# Schematic_KeyScreen.net
KiCad netlist of a schematic drawn in Altium Designer
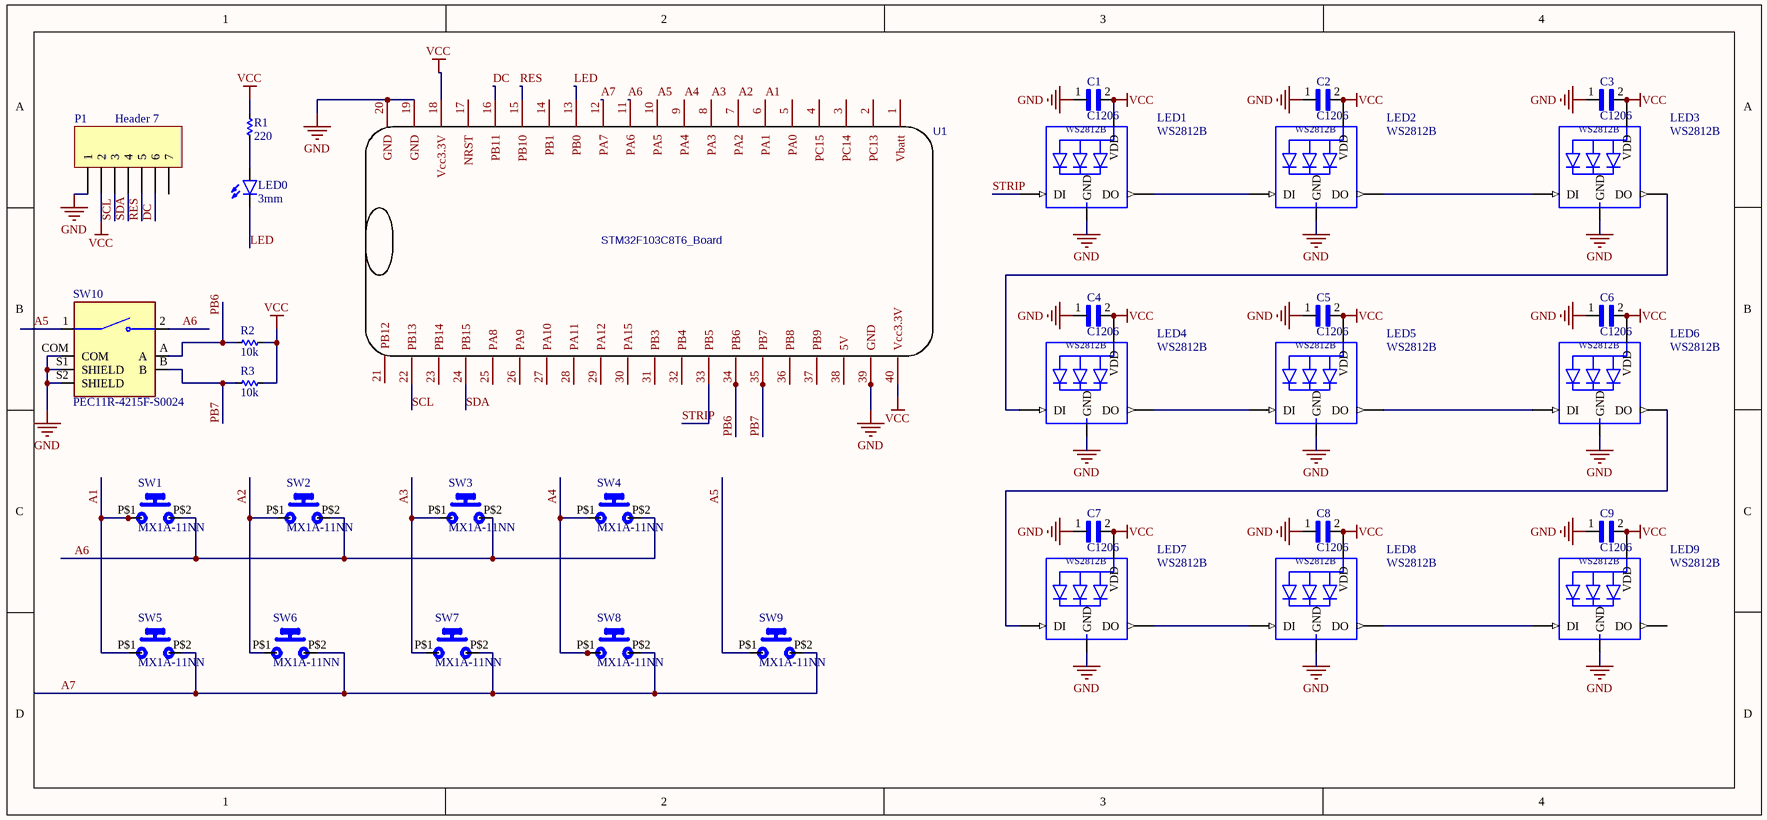
[diagram p0: Schematic_KeyScreen.SchDoc]

(export (version "E")
  (design (tool "Eeschema 10.0.6"))
  (components
    (comp (ref "C1")
      (value "C1206")
      (footprint "SnapEDApcb:CAPC3216X110N")
      (description "1ÂµF Â±10% 50V Ceramic Capacitor X7R 1206 _3216 Metric_")
      (fields (field (name "MP") "C1206C105K5RACTU") (field (name "MF") "KEMET"))
      (libsource (lib "SnapEDAsch") (part "C1206C105K5RACTU"))
    )
    (comp (ref "C2")
      (value "C1206")
      (footprint "SnapEDApcb:CAPC3216X110N")
      (description "1ÂµF Â±10% 50V Ceramic Capacitor X7R 1206 _3216 Metric_")
      (fields (field (name "MP") "C1206C105K5RACTU") (field (name "MF") "KEMET"))
      (libsource (lib "SnapEDAsch") (part "C1206C105K5RACTU"))
    )
    (comp (ref "C3")
      (value "C1206")
      (footprint "SnapEDApcb:CAPC3216X110N")
      (description "1ÂµF Â±10% 50V Ceramic Capacitor X7R 1206 _3216 Metric_")
      (fields (field (name "MP") "C1206C105K5RACTU") (field (name "MF") "KEMET"))
      (libsource (lib "SnapEDAsch") (part "C1206C105K5RACTU"))
    )
    (comp (ref "C4")
      (value "C1206")
      (footprint "SnapEDApcb:CAPC3216X110N")
      (description "1ÂµF Â±10% 50V Ceramic Capacitor X7R 1206 _3216 Metric_")
      (fields (field (name "MP") "C1206C105K5RACTU") (field (name "MF") "KEMET"))
      (libsource (lib "SnapEDAsch") (part "C1206C105K5RACTU"))
    )
    (comp (ref "C5")
      (value "C1206")
      (footprint "SnapEDApcb:CAPC3216X110N")
      (description "1ÂµF Â±10% 50V Ceramic Capacitor X7R 1206 _3216 Metric_")
      (fields (field (name "MP") "C1206C105K5RACTU") (field (name "MF") "KEMET"))
      (libsource (lib "SnapEDAsch") (part "C1206C105K5RACTU"))
    )
    (comp (ref "C6")
      (value "C1206")
      (footprint "SnapEDApcb:CAPC3216X110N")
      (description "1ÂµF Â±10% 50V Ceramic Capacitor X7R 1206 _3216 Metric_")
      (fields (field (name "MP") "C1206C105K5RACTU") (field (name "MF") "KEMET"))
      (libsource (lib "SnapEDAsch") (part "C1206C105K5RACTU"))
    )
    (comp (ref "C7")
      (value "C1206")
      (footprint "Miscellaneous Devices:3.2X1.6X1.1")
      (description "1ÂµF Â±10% 50V Ceramic Capacitor X7R 1206 _3216 Metric_")
      (fields (field (name "MP") "C1206C105K5RACTU") (field (name "MF") "KEMET"))
      (libsource (lib "SnapEDAsch") (part "C1206C105K5RACTU"))
    )
    (comp (ref "C8")
      (value "C1206")
      (footprint "Miscellaneous Devices:3.2X1.6X1.1")
      (description "1ÂµF Â±10% 50V Ceramic Capacitor X7R 1206 _3216 Metric_")
      (fields (field (name "MP") "C1206C105K5RACTU") (field (name "MF") "KEMET"))
      (libsource (lib "SnapEDAsch") (part "C1206C105K5RACTU"))
    )
    (comp (ref "C9")
      (value "C1206")
      (footprint "SnapEDApcb:CAPC3216X110N")
      (description "1ÂµF Â±10% 50V Ceramic Capacitor X7R 1206 _3216 Metric_")
      (fields (field (name "MP") "C1206C105K5RACTU") (field (name "MF") "KEMET"))
      (libsource (lib "SnapEDAsch") (part "C1206C105K5RACTU"))
    )
    (comp (ref "LED0")
      (value "3mm")
      (footprint "LED3MM")
      (description "Green 569nm LED Indication - Discrete 1.9V Radial")
      (fields (field (name "MP") "TLLG4400") (field (name "MF") "Vishay Semiconductors"))
      (libsource (lib "TLLG4400") (part "TLLG4400"))
    )
    (comp (ref "LED1")
      (value "WS2812B")
      (footprint "SnapEDApcb:WS2812B")
      (description "Raspberry Pi HAT _40 pin_ Wheeled Robotics Kit")
      (fields (field (name "MF") "SparkFun Electronics"))
      (libsource (lib "SnapEDAsch") (part "WS2812B"))
    )
    (comp (ref "LED2")
      (value "WS2812B")
      (footprint "SnapEDApcb:WS2812B")
      (description "Raspberry Pi HAT _40 pin_ Wheeled Robotics Kit")
      (fields (field (name "MF") "SparkFun Electronics"))
      (libsource (lib "SnapEDAsch") (part "WS2812B"))
    )
    (comp (ref "LED3")
      (value "WS2812B")
      (footprint "SnapEDApcb:WS2812B")
      (description "Raspberry Pi HAT _40 pin_ Wheeled Robotics Kit")
      (fields (field (name "MF") "SparkFun Electronics"))
      (libsource (lib "SnapEDAsch") (part "WS2812B"))
    )
    (comp (ref "LED4")
      (value "WS2812B")
      (footprint "SnapEDApcb:WS2812B")
      (description "Raspberry Pi HAT _40 pin_ Wheeled Robotics Kit")
      (fields (field (name "MF") "SparkFun Electronics"))
      (libsource (lib "SnapEDAsch") (part "WS2812B"))
    )
    (comp (ref "LED5")
      (value "WS2812B")
      (footprint "SnapEDApcb:WS2812B")
      (description "Raspberry Pi HAT _40 pin_ Wheeled Robotics Kit")
      (fields (field (name "MF") "SparkFun Electronics"))
      (libsource (lib "SnapEDAsch") (part "WS2812B"))
    )
    (comp (ref "LED6")
      (value "WS2812B")
      (footprint "SnapEDApcb:WS2812B")
      (description "Raspberry Pi HAT _40 pin_ Wheeled Robotics Kit")
      (fields (field (name "MF") "SparkFun Electronics"))
      (libsource (lib "SnapEDAsch") (part "WS2812B"))
    )
    (comp (ref "LED7")
      (value "WS2812B")
      (footprint "SnapEDApcb:WS2812B")
      (description "Raspberry Pi HAT _40 pin_ Wheeled Robotics Kit")
      (fields (field (name "MF") "SparkFun Electronics"))
      (libsource (lib "SnapEDAsch") (part "WS2812B"))
    )
    (comp (ref "LED8")
      (value "WS2812B")
      (footprint "SnapEDApcb:WS2812B")
      (description "Raspberry Pi HAT _40 pin_ Wheeled Robotics Kit")
      (fields (field (name "MF") "SparkFun Electronics"))
      (libsource (lib "SnapEDAsch") (part "WS2812B"))
    )
    (comp (ref "LED9")
      (value "WS2812B")
      (footprint "SnapEDApcb:WS2812B")
      (description "Raspberry Pi HAT _40 pin_ Wheeled Robotics Kit")
      (fields (field (name "MF") "SparkFun Electronics"))
      (libsource (lib "SnapEDAsch") (part "WS2812B"))
    )
    (comp (ref "P1")
      (value "Header 7")
      (footprint "HDR1X7")
      (description "Header, 7-Pin")
      (fields (field (name "PUBLISHER") "Altium Limited"))
      (libsource (lib "Miscellaneous Connectors") (part "Header 7"))
    )
    (comp (ref "R1")
      (value "220")
      (footprint "RESC3116X65N:RESC3116X65N")
      (description "Resistor")
      (fields
        (field (name "MANUFACTURER") "Generic Components")
        (field (name "PUBLISHER") "Altium Hobart Technology Centre")
      )
      (libsource (lib "LIBRARY-123") (part "Res-SMD"))
    )
    (comp (ref "R2")
      (value "10k")
      (footprint "RESC3116X65N:RESC3116X65N")
      (description "Resistor")
      (fields
        (field (name "MANUFACTURER") "Generic Components")
        (field (name "PUBLISHER") "Altium Hobart Technology Centre")
      )
      (libsource (lib "LIBRARY-123") (part "Res-SMD"))
    )
    (comp (ref "R3")
      (value "10k")
      (footprint "RESC3116X65N:RESC3116X65N")
      (description "Resistor")
      (fields
        (field (name "MANUFACTURER") "Generic Components")
        (field (name "PUBLISHER") "Altium Hobart Technology Centre")
      )
      (libsource (lib "LIBRARY-123") (part "Res-SMD"))
    )
    (comp (ref "SW1")
      (value "MX1A-11NN")
      (footprint "CHERRY_MX1A-11NN_SWITCH:CHERRY_MX1A-11NN_SWITCH")
      (description "Pushbutton Switch SPST-NO Keyswitch Panel Mount, Front")
      (fields (field (name "MF") "Cherry"))
      (libsource (lib "MX1A-11NN") (part "MX1A-11NN"))
    )
    (comp (ref "SW2")
      (value "MX1A-11NN")
      (footprint "CHERRY_MX1A-11NN_SWITCH:CHERRY_MX1A-11NN_SWITCH")
      (description "Pushbutton Switch SPST-NO Keyswitch Panel Mount, Front")
      (fields (field (name "MF") "Cherry"))
      (libsource (lib "MX1A-11NN") (part "MX1A-11NN"))
    )
    (comp (ref "SW3")
      (value "MX1A-11NN")
      (footprint "CHERRY_MX1A-11NN_SWITCH:CHERRY_MX1A-11NN_SWITCH")
      (description "Pushbutton Switch SPST-NO Keyswitch Panel Mount, Front")
      (fields (field (name "MF") "Cherry"))
      (libsource (lib "MX1A-11NN") (part "MX1A-11NN"))
    )
    (comp (ref "SW4")
      (value "MX1A-11NN")
      (footprint "CHERRY_MX1A-11NN_SWITCH:CHERRY_MX1A-11NN_SWITCH")
      (description "Pushbutton Switch SPST-NO Keyswitch Panel Mount, Front")
      (fields (field (name "MF") "Cherry"))
      (libsource (lib "MX1A-11NN") (part "MX1A-11NN"))
    )
    (comp (ref "SW5")
      (value "MX1A-11NN")
      (footprint "CHERRY_MX1A-11NN_SWITCH:CHERRY_MX1A-11NN_SWITCH")
      (description "Pushbutton Switch SPST-NO Keyswitch Panel Mount, Front")
      (fields (field (name "MF") "Cherry"))
      (libsource (lib "MX1A-11NN") (part "MX1A-11NN"))
    )
    (comp (ref "SW6")
      (value "MX1A-11NN")
      (footprint "CHERRY_MX1A-11NN_SWITCH:CHERRY_MX1A-11NN_SWITCH")
      (description "Pushbutton Switch SPST-NO Keyswitch Panel Mount, Front")
      (fields (field (name "MF") "Cherry"))
      (libsource (lib "MX1A-11NN") (part "MX1A-11NN"))
    )
    (comp (ref "SW7")
      (value "MX1A-11NN")
      (footprint "CHERRY_MX1A-11NN_SWITCH:CHERRY_MX1A-11NN_SWITCH")
      (description "Pushbutton Switch SPST-NO Keyswitch Panel Mount, Front")
      (fields (field (name "MF") "Cherry"))
      (libsource (lib "MX1A-11NN") (part "MX1A-11NN"))
    )
    (comp (ref "SW8")
      (value "MX1A-11NN")
      (footprint "CHERRY_MX1A-11NN_SWITCH:CHERRY_MX1A-11NN_SWITCH")
      (description "Pushbutton Switch SPST-NO Keyswitch Panel Mount, Front")
      (fields (field (name "MF") "Cherry"))
      (libsource (lib "MX1A-11NN") (part "MX1A-11NN"))
    )
    (comp (ref "SW9")
      (value "MX1A-11NN")
      (footprint "CHERRY_MX1A-11NN_SWITCH:CHERRY_MX1A-11NN_SWITCH")
      (description "Pushbutton Switch SPST-NO Keyswitch Panel Mount, Front")
      (fields (field (name "MF") "Cherry"))
      (libsource (lib "MX1A-11NN") (part "MX1A-11NN"))
    )
    (comp (ref "SW10")
      (value "PEC11R-4215F-S0024")
      (footprint "XDCR_PEC11R-4215F-S0024:XDCR_PEC11R-4215F-S0024")
      (description "Incremental Encoder, 12 Mm, Contact Rating 10 Ma - 5 Vdc")
      (libsource (lib "PEC11R-4215F-S0024") (part "PEC11R-4215F-S0024"))
    )
    (comp (ref "U1")
      (value "STM32F103C8T6_Board")
      (footprint "Blue_pill:PCBComponent_1")
      (fields (field (name "MANUFACTURER PART") "STM32Duino") (field (name "CONTRIBUTOR") "Johan_a"))
      (libsource (lib "SCHEMATIC-LQFP") (part "STM32F103C8T6_Blue pill"))
    )
  )
  (nets
    (net (code "1") (name "/A1") (class "Default")
      (node (ref "SW1") (pin "P$1") (pinfunction "P_P$1") (pintype "passive"))
      (node (ref "SW5") (pin "P$1") (pinfunction "P_P$1") (pintype "passive"))
      (node (ref "U1") (pin "6") (pinfunction "PA1_6") (pintype "passive"))
    )
    (net (code "2") (name "/A2") (class "Default")
      (node (ref "SW2") (pin "P$1") (pinfunction "P_P$1") (pintype "passive"))
      (node (ref "SW6") (pin "P$1") (pinfunction "P_P$1") (pintype "passive"))
      (node (ref "U1") (pin "7") (pinfunction "PA2_7") (pintype "passive"))
    )
    (net (code "3") (name "/A3") (class "Default")
      (node (ref "SW3") (pin "P$1") (pinfunction "P_P$1") (pintype "passive"))
      (node (ref "SW7") (pin "P$1") (pinfunction "P_P$1") (pintype "passive"))
      (node (ref "U1") (pin "8") (pinfunction "PA3_8") (pintype "passive"))
    )
    (net (code "4") (name "/A4") (class "Default")
      (node (ref "SW4") (pin "P$1") (pinfunction "P_P$1") (pintype "passive"))
      (node (ref "SW8") (pin "P$1") (pinfunction "P_P$1") (pintype "passive"))
      (node (ref "U1") (pin "9") (pinfunction "PA4_9") (pintype "passive"))
    )
    (net (code "5") (name "/A5") (class "Default")
      (node (ref "SW10") (pin "1") (pinfunction "1_1") (pintype "passive"))
      (node (ref "SW9") (pin "P$1") (pinfunction "P_P$1") (pintype "passive"))
      (node (ref "U1") (pin "10") (pinfunction "PA5_10") (pintype "passive"))
    )
    (net (code "6") (name "/A6") (class "Default")
      (node (ref "SW1") (pin "P$2") (pinfunction "S_P$2") (pintype "passive"))
      (node (ref "SW10") (pin "2") (pinfunction "2_2") (pintype "passive"))
      (node (ref "SW2") (pin "P$2") (pinfunction "S_P$2") (pintype "passive"))
      (node (ref "SW3") (pin "P$2") (pinfunction "S_P$2") (pintype "passive"))
      (node (ref "SW4") (pin "P$2") (pinfunction "S_P$2") (pintype "passive"))
      (node (ref "U1") (pin "11") (pinfunction "PA6_11") (pintype "passive"))
    )
    (net (code "7") (name "/A7") (class "Default")
      (node (ref "SW5") (pin "P$2") (pinfunction "S_P$2") (pintype "passive"))
      (node (ref "SW6") (pin "P$2") (pinfunction "S_P$2") (pintype "passive"))
      (node (ref "SW7") (pin "P$2") (pinfunction "S_P$2") (pintype "passive"))
      (node (ref "SW8") (pin "P$2") (pinfunction "S_P$2") (pintype "passive"))
      (node (ref "SW9") (pin "P$2") (pinfunction "S_P$2") (pintype "passive"))
      (node (ref "U1") (pin "12") (pinfunction "PA7_12") (pintype "passive"))
    )
    (net (code "8") (name "/DC") (class "Default")
      (node (ref "P1") (pin "6") (pinfunction "6_6") (pintype "passive"))
      (node (ref "U1") (pin "16") (pinfunction "PB11_16") (pintype "passive"))
    )
    (net (code "9") (name "/LED") (class "Default")
      (node (ref "LED0") (pin "K") (pinfunction "C_K") (pintype "passive"))
      (node (ref "U1") (pin "13") (pinfunction "PB0_13") (pintype "passive"))
    )
    (net (code "10") (name "/PB6") (class "Default")
      (node (ref "R2") (pin "2") (pinfunction "2_2") (pintype "passive"))
      (node (ref "SW10") (pin "A") (pinfunction "A_A") (pintype "passive"))
      (node (ref "U1") (pin "34") (pinfunction "PB6_34") (pintype "passive"))
    )
    (net (code "11") (name "/PB7") (class "Default")
      (node (ref "R3") (pin "2") (pinfunction "2_2") (pintype "passive"))
      (node (ref "SW10") (pin "B") (pinfunction "B_B") (pintype "passive"))
      (node (ref "U1") (pin "35") (pinfunction "PB7_35") (pintype "passive"))
    )
    (net (code "12") (name "/RES") (class "Default")
      (node (ref "P1") (pin "5") (pinfunction "5_5") (pintype "passive"))
      (node (ref "U1") (pin "15") (pinfunction "PB10_15") (pintype "passive"))
    )
    (net (code "13") (name "/SCL") (class "Default")
      (node (ref "P1") (pin "3") (pinfunction "3_3") (pintype "passive"))
      (node (ref "U1") (pin "22") (pinfunction "PB13_22") (pintype "passive"))
    )
    (net (code "14") (name "/SDA") (class "Default")
      (node (ref "P1") (pin "4") (pinfunction "4_4") (pintype "passive"))
      (node (ref "U1") (pin "24") (pinfunction "PB15_24") (pintype "passive"))
    )
    (net (code "15") (name "/STRIP") (class "Default")
      (node (ref "LED1") (pin "4-DIN") (pinfunction "DI_4-DIN") (pintype "input"))
      (node (ref "U1") (pin "33") (pinfunction "PB5_33") (pintype "passive"))
    )
    (net (code "16") (name "GND") (class "Default")
      (node (ref "C1") (pin "1") (pinfunction "1_1") (pintype "passive"))
      (node (ref "C2") (pin "1") (pinfunction "1_1") (pintype "passive"))
      (node (ref "C3") (pin "1") (pinfunction "1_1") (pintype "passive"))
      (node (ref "C4") (pin "1") (pinfunction "1_1") (pintype "passive"))
      (node (ref "C5") (pin "1") (pinfunction "1_1") (pintype "passive"))
      (node (ref "C6") (pin "1") (pinfunction "1_1") (pintype "passive"))
      (node (ref "C7") (pin "1") (pinfunction "1_1") (pintype "passive"))
      (node (ref "C8") (pin "1") (pinfunction "1_1") (pintype "passive"))
      (node (ref "C9") (pin "1") (pinfunction "1_1") (pintype "passive"))
      (node (ref "LED1") (pin "3-GND") (pinfunction "GND_3-GND") (pintype "power_in"))
      (node (ref "LED2") (pin "3-GND") (pinfunction "GND_3-GND") (pintype "power_in"))
      (node (ref "LED3") (pin "3-GND") (pinfunction "GND_3-GND") (pintype "power_in"))
      (node (ref "LED4") (pin "3-GND") (pinfunction "GND_3-GND") (pintype "power_in"))
      (node (ref "LED5") (pin "3-GND") (pinfunction "GND_3-GND") (pintype "power_in"))
      (node (ref "LED6") (pin "3-GND") (pinfunction "GND_3-GND") (pintype "power_in"))
      (node (ref "LED7") (pin "3-GND") (pinfunction "GND_3-GND") (pintype "power_in"))
      (node (ref "LED8") (pin "3-GND") (pinfunction "GND_3-GND") (pintype "power_in"))
      (node (ref "LED9") (pin "3-GND") (pinfunction "GND_3-GND") (pintype "power_in"))
      (node (ref "P1") (pin "1") (pinfunction "1_1") (pintype "passive"))
      (node (ref "SW10") (pin "COM") (pinfunction "COM_COM") (pintype "passive"))
      (node (ref "SW10") (pin "S1") (pinfunction "SHIELD_S1") (pintype "passive"))
      (node (ref "SW10") (pin "S2") (pinfunction "SHIELD_S2") (pintype "passive"))
      (node (ref "U1") (pin "19") (pinfunction "GND_19") (pintype "passive"))
      (node (ref "U1") (pin "20") (pinfunction "GND_20") (pintype "passive"))
      (node (ref "U1") (pin "39") (pinfunction "GND_39") (pintype "passive"))
    )
    (net (code "17") (name "Net-(LED0-PadA)") (class "Default")
      (node (ref "LED0") (pin "A") (pinfunction "A_A") (pintype "passive"))
      (node (ref "R1") (pin "2") (pinfunction "2_2") (pintype "passive"))
    )
    (net (code "18") (name "Net-(LED1-DO)") (class "Default")
      (node (ref "LED1") (pin "2-DOUT") (pinfunction "DO_2-DOUT") (pintype "output"))
      (node (ref "LED2") (pin "4-DIN") (pinfunction "DI_4-DIN") (pintype "input"))
    )
    (net (code "19") (name "Net-(LED2-DO)") (class "Default")
      (node (ref "LED2") (pin "2-DOUT") (pinfunction "DO_2-DOUT") (pintype "output"))
      (node (ref "LED3") (pin "4-DIN") (pinfunction "DI_4-DIN") (pintype "input"))
    )
    (net (code "20") (name "Net-(LED3-DO)") (class "Default")
      (node (ref "LED3") (pin "2-DOUT") (pinfunction "DO_2-DOUT") (pintype "output"))
      (node (ref "LED4") (pin "4-DIN") (pinfunction "DI_4-DIN") (pintype "input"))
    )
    (net (code "21") (name "Net-(LED4-DO)") (class "Default")
      (node (ref "LED4") (pin "2-DOUT") (pinfunction "DO_2-DOUT") (pintype "output"))
      (node (ref "LED5") (pin "4-DIN") (pinfunction "DI_4-DIN") (pintype "input"))
    )
    (net (code "22") (name "Net-(LED5-DO)") (class "Default")
      (node (ref "LED5") (pin "2-DOUT") (pinfunction "DO_2-DOUT") (pintype "output"))
      (node (ref "LED6") (pin "4-DIN") (pinfunction "DI_4-DIN") (pintype "input"))
    )
    (net (code "23") (name "Net-(LED6-DO)") (class "Default")
      (node (ref "LED6") (pin "2-DOUT") (pinfunction "DO_2-DOUT") (pintype "output"))
      (node (ref "LED7") (pin "4-DIN") (pinfunction "DI_4-DIN") (pintype "input"))
    )
    (net (code "24") (name "Net-(LED7-DO)") (class "Default")
      (node (ref "LED7") (pin "2-DOUT") (pinfunction "DO_2-DOUT") (pintype "output"))
      (node (ref "LED8") (pin "4-DIN") (pinfunction "DI_4-DIN") (pintype "input"))
    )
    (net (code "25") (name "Net-(LED8-DO)") (class "Default")
      (node (ref "LED8") (pin "2-DOUT") (pinfunction "DO_2-DOUT") (pintype "output"))
      (node (ref "LED9") (pin "4-DIN") (pinfunction "DI_4-DIN") (pintype "input"))
    )
    (net (code "26") (name "VCC") (class "Default")
      (node (ref "C1") (pin "2") (pinfunction "2_2") (pintype "passive"))
      (node (ref "C2") (pin "2") (pinfunction "2_2") (pintype "passive"))
      (node (ref "C3") (pin "2") (pinfunction "2_2") (pintype "passive"))
      (node (ref "C4") (pin "2") (pinfunction "2_2") (pintype "passive"))
      (node (ref "C5") (pin "2") (pinfunction "2_2") (pintype "passive"))
      (node (ref "C6") (pin "2") (pinfunction "2_2") (pintype "passive"))
      (node (ref "C7") (pin "2") (pinfunction "2_2") (pintype "passive"))
      (node (ref "C8") (pin "2") (pinfunction "2_2") (pintype "passive"))
      (node (ref "C9") (pin "2") (pinfunction "2_2") (pintype "passive"))
      (node (ref "LED1") (pin "1-VDD") (pinfunction "VDD_1-VDD") (pintype "power_in"))
      (node (ref "LED2") (pin "1-VDD") (pinfunction "VDD_1-VDD") (pintype "power_in"))
      (node (ref "LED3") (pin "1-VDD") (pinfunction "VDD_1-VDD") (pintype "power_in"))
      (node (ref "LED4") (pin "1-VDD") (pinfunction "VDD_1-VDD") (pintype "power_in"))
      (node (ref "LED5") (pin "1-VDD") (pinfunction "VDD_1-VDD") (pintype "power_in"))
      (node (ref "LED6") (pin "1-VDD") (pinfunction "VDD_1-VDD") (pintype "power_in"))
      (node (ref "LED7") (pin "1-VDD") (pinfunction "VDD_1-VDD") (pintype "power_in"))
      (node (ref "LED8") (pin "1-VDD") (pinfunction "VDD_1-VDD") (pintype "power_in"))
      (node (ref "LED9") (pin "1-VDD") (pinfunction "VDD_1-VDD") (pintype "power_in"))
      (node (ref "P1") (pin "2") (pinfunction "2_2") (pintype "passive"))
      (node (ref "R1") (pin "1") (pinfunction "1_1") (pintype "passive"))
      (node (ref "R2") (pin "1") (pinfunction "1_1") (pintype "passive"))
      (node (ref "R3") (pin "1") (pinfunction "1_1") (pintype "passive"))
      (node (ref "U1") (pin "18") (pinfunction "Vcc3.3V_18") (pintype "passive"))
      (node (ref "U1") (pin "40") (pinfunction "Vcc3.3V_40") (pintype "passive"))
    )
    (net (code "27") (name "unconnected-(LED9-DO-Pad2-DOUT)") (class "Default")
      (node (ref "LED9") (pin "2-DOUT") (pinfunction "DO_2-DOUT") (pintype "output"))
    )
    (net (code "28") (name "unconnected-(P1-Pad7)") (class "Default")
      (node (ref "P1") (pin "7") (pinfunction "7_7") (pintype "passive"))
    )
    (net (code "29") (name "unconnected-(U1-5V-Pad38)") (class "Default")
      (node (ref "U1") (pin "38") (pinfunction "5V_38") (pintype "passive"))
    )
    (net (code "30") (name "unconnected-(U1-NRST-Pad17)") (class "Default")
      (node (ref "U1") (pin "17") (pinfunction "NRST_17") (pintype "passive"))
    )
    (net (code "31") (name "unconnected-(U1-PA0-Pad5)") (class "Default")
      (node (ref "U1") (pin "5") (pinfunction "PA0_5") (pintype "passive"))
    )
    (net (code "32") (name "unconnected-(U1-PA8-Pad25)") (class "Default")
      (node (ref "U1") (pin "25") (pinfunction "PA8_25") (pintype "passive"))
    )
    (net (code "33") (name "unconnected-(U1-PA9-Pad26)") (class "Default")
      (node (ref "U1") (pin "26") (pinfunction "PA9_26") (pintype "passive"))
    )
    (net (code "34") (name "unconnected-(U1-PA10-Pad27)") (class "Default")
      (node (ref "U1") (pin "27") (pinfunction "PA10_27") (pintype "passive"))
    )
    (net (code "35") (name "unconnected-(U1-PA11-Pad28)") (class "Default")
      (node (ref "U1") (pin "28") (pinfunction "PA11_28") (pintype "passive"))
    )
    (net (code "36") (name "unconnected-(U1-PA12-Pad29)") (class "Default")
      (node (ref "U1") (pin "29") (pinfunction "PA12_29") (pintype "passive"))
    )
    (net (code "37") (name "unconnected-(U1-PA15-Pad30)") (class "Default")
      (node (ref "U1") (pin "30") (pinfunction "PA15_30") (pintype "passive"))
    )
    (net (code "38") (name "unconnected-(U1-PB1-Pad14)") (class "Default")
      (node (ref "U1") (pin "14") (pinfunction "PB1_14") (pintype "passive"))
    )
    (net (code "39") (name "unconnected-(U1-PB3-Pad31)") (class "Default")
      (node (ref "U1") (pin "31") (pinfunction "PB3_31") (pintype "passive"))
    )
    (net (code "40") (name "unconnected-(U1-PB4-Pad32)") (class "Default")
      (node (ref "U1") (pin "32") (pinfunction "PB4_32") (pintype "passive"))
    )
    (net (code "41") (name "unconnected-(U1-PB8-Pad36)") (class "Default")
      (node (ref "U1") (pin "36") (pinfunction "PB8_36") (pintype "passive"))
    )
    (net (code "42") (name "unconnected-(U1-PB9-Pad37)") (class "Default")
      (node (ref "U1") (pin "37") (pinfunction "PB9_37") (pintype "passive"))
    )
    (net (code "43") (name "unconnected-(U1-PB12-Pad21)") (class "Default")
      (node (ref "U1") (pin "21") (pinfunction "PB12_21") (pintype "passive"))
    )
    (net (code "44") (name "unconnected-(U1-PB14-Pad23)") (class "Default")
      (node (ref "U1") (pin "23") (pinfunction "PB14_23") (pintype "passive"))
    )
    (net (code "45") (name "unconnected-(U1-PC13-Pad2)") (class "Default")
      (node (ref "U1") (pin "2") (pinfunction "PC13_2") (pintype "passive"))
    )
    (net (code "46") (name "unconnected-(U1-PC14-Pad3)") (class "Default")
      (node (ref "U1") (pin "3") (pinfunction "PC14_3") (pintype "passive"))
    )
    (net (code "47") (name "unconnected-(U1-PC15-Pad4)") (class "Default")
      (node (ref "U1") (pin "4") (pinfunction "PC15_4") (pintype "passive"))
    )
    (net (code "48") (name "unconnected-(U1-Vbatt-Pad1)") (class "Default")
      (node (ref "U1") (pin "1") (pinfunction "Vbatt_1") (pintype "passive"))
    )
  )
)
